# Peripherals.net
KiCad netlist of a schematic drawn in Altium Designer
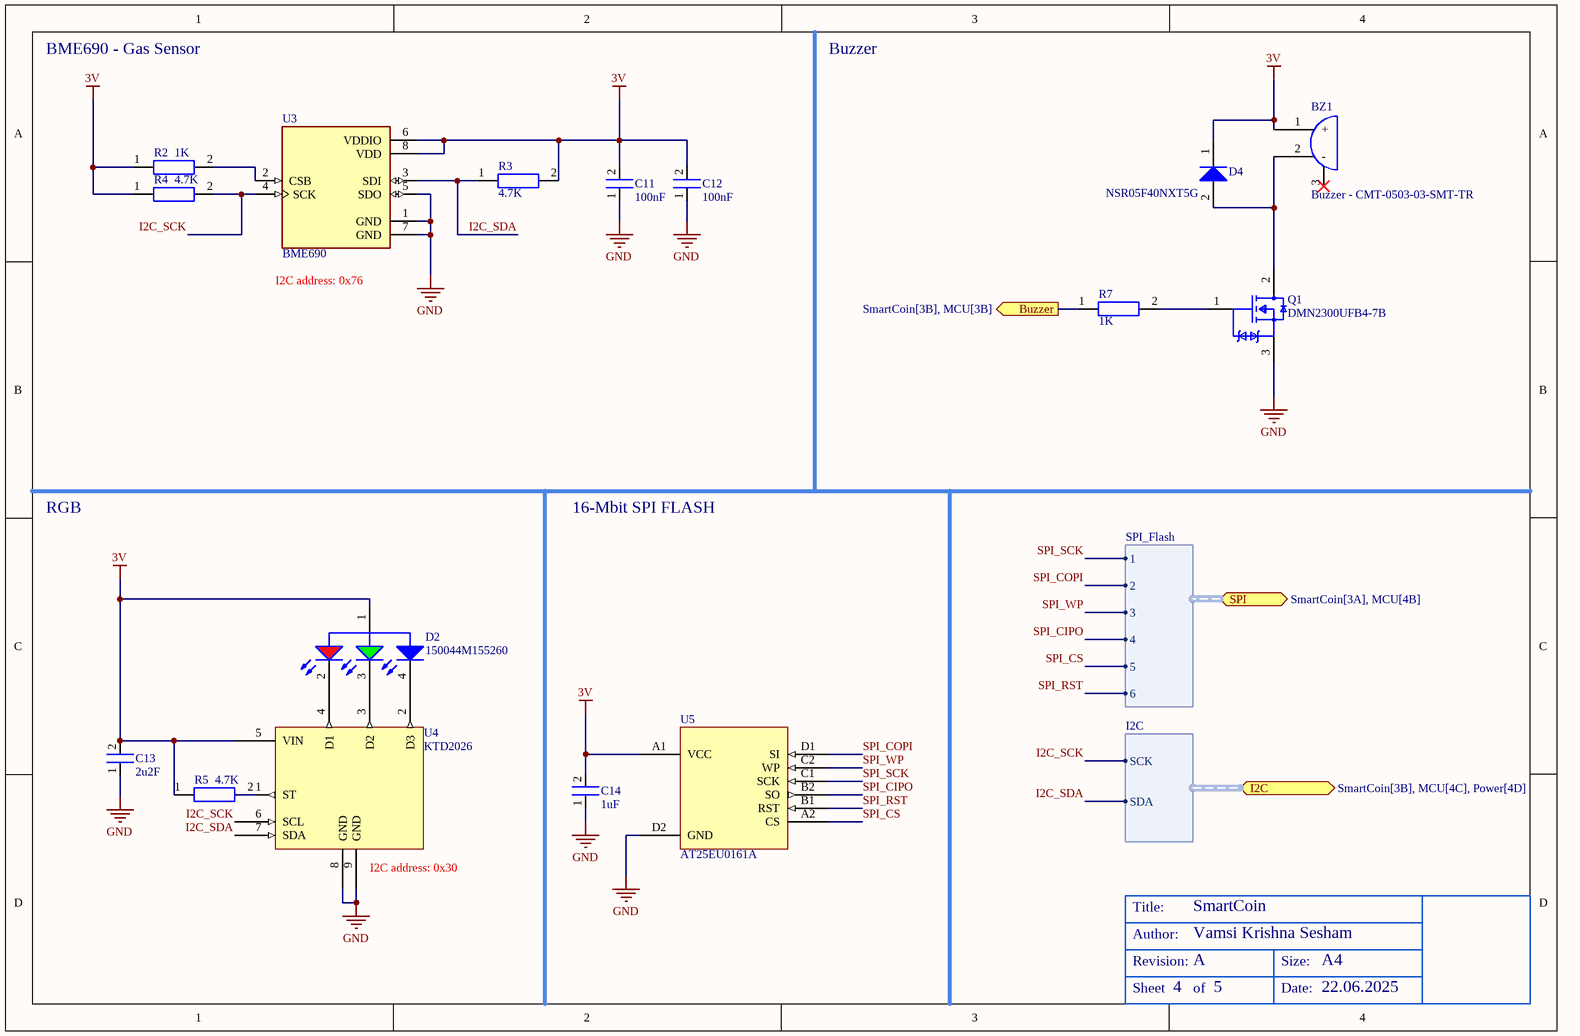
[diagram p0: Peripherals.SchDoc]

(export (version "E")
  (design (tool "Eeschema 10.0.6"))
  (components
    (comp (ref "BZ1")
      (value "Buzzer - CMT-0503-03-SMT-TR")
      (footprint "Buzzer - CMT-0503-03-SMT-TR")
      (description "MAGNETIC BUZZER TRANSDUCER")
      (libsource (lib "SmartCoin") (part "Buzzer - CMT-0503-03-SMT-TR"))
    )
    (comp (ref "C11")
      (value "100nF")
      (footprint "Capacitor - 0201")
      (libsource (lib "SmartCoin") (part "Capacitor - 0201"))
    )
    (comp (ref "C12")
      (value "100nF")
      (footprint "Capacitor - 0201")
      (libsource (lib "SmartCoin") (part "Capacitor - 0201"))
    )
    (comp (ref "C13")
      (value "2u2F")
      (footprint "Capacitor - 0201")
      (libsource (lib "SmartCoin") (part "Capacitor - 0201"))
    )
    (comp (ref "C14")
      (value "1uF")
      (footprint "Capacitor - 0201")
      (libsource (lib "SmartCoin") (part "Capacitor - 0201"))
    )
    (comp (ref "D2")
      (value "150044M155260")
      (footprint "WL-SFCC_0404_150044M155260")
      (description "150044M155260 WL-SFCC SMT Full-color Chip LED compact")
      (libsource (lib "Altium Content Vault") (part "WL-SFCC_150044M155260"))
    )
    (comp (ref "D4")
      (value "NSR05F40NXT5G")
      (footprint "ONSC-DSN-2-152AC-01_V")
      (description "Schottky Barrier Diode, 2-Pin DSN, Pb-Free, Tape and Reel")
      (fields (field (name "MANUFACTURER") "On Semiconductor"))
      (libsource (lib "Altium Content Vault") (part "ONSC-D-K1A2-2"))
    )
    (comp (ref "Q1")
      (value "DMN2300UFB4-7B")
      (footprint "FP-X2-DFN1006-3-MFG")
      (description "MOSFET N-CH 20V 1.3A 3DFN")
      (fields
        (field (name "MANUFACTURER") "Diodes Inc.")
        (field (name "OCTOPART") "https://octopart.com/dmn2300ufb4-7b-diodes+inc.-21789371")
      )
      (libsource (lib "Altium Content Vault") (part "a29196b179eec536a16aaf037fa858d"))
    )
    (comp (ref "R2")
      (value "1K")
      (footprint "Resistor - 0201")
      (libsource (lib "SmartCoin") (part "Resistor - 0201"))
    )
    (comp (ref "R3")
      (value "4.7K")
      (footprint "Resistor - 0201")
      (libsource (lib "SmartCoin") (part "Resistor - 0201"))
    )
    (comp (ref "R4")
      (value "4.7K")
      (footprint "Resistor - 0201")
      (libsource (lib "SmartCoin") (part "Resistor - 0201"))
    )
    (comp (ref "R5")
      (value "4.7K")
      (footprint "Resistor - 0201")
      (libsource (lib "SmartCoin") (part "Resistor - 0201"))
    )
    (comp (ref "R7")
      (value "1K")
      (footprint "Resistor - 0201")
      (libsource (lib "SmartCoin") (part "Resistor - 0201"))
    )
    (comp (ref "U3")
      (value "BME690")
      (footprint "IC_BME688")
      (description "Gas sensor measuring relative humidity, barometric pressure, ambient temperature and gas (VOC)")
      (fields (field (name "MP") "BME688"))
      (libsource (lib "Vamsi Krishna Sesham") (part "BME688"))
    )
    (comp (ref "U4")
      (value "KTD2026")
      (footprint "KTD2026")
      (description "3-CHANNEL Rgb Led Driver With I2C")
      (libsource (lib "SmartCoin") (part "KTD2026"))
    )
    (comp (ref "U5")
      (value "AT25EU0161A")
      (footprint "AT25EU0161A")
      (description "16-Mbit, Ultra-Low Energy Serial Flash Memory")
      (libsource (lib "SmartCoin") (part "AT25EU0161A"))
    )
  )
  (nets
    (net (code "3") (name "/Buzzer") (class "Default") (node (ref "R7") (pin "1") (pintype "passive")))
    (net (code "4") (name "/I2C_SCK") (class "Default")
      (node (ref "R4") (pin "2") (pintype "passive"))
      (node (ref "U3") (pin "4") (pinfunction "SCK_4") (pintype "input"))
      (node (ref "U4") (pin "6") (pinfunction "SCL_6") (pintype "input"))
    )
    (net (code "5") (name "/I2C_SDA") (class "Default")
      (node (ref "R3") (pin "1") (pintype "passive"))
      (node (ref "U3") (pin "3") (pinfunction "SDI_3") (pintype "bidirectional"))
      (node (ref "U4") (pin "7") (pinfunction "SDA_7") (pintype "input"))
    )
    (net (code "6") (name "/SPI_CIPO") (class "Default")
      (node (ref "U5") (pin "B2") (pinfunction "SO_B2") (pintype "output"))
    )
    (net (code "7") (name "/SPI_COPI") (class "Default")
      (node (ref "U5") (pin "D1") (pinfunction "SI_D1") (pintype "input"))
    )
    (net (code "8") (name "/SPI_CS") (class "Default")
      (node (ref "U5") (pin "A2") (pinfunction "CS_A2") (pintype "passive"))
    )
    (net (code "9") (name "/SPI_RST") (class "Default")
      (node (ref "U5") (pin "B1") (pinfunction "RST_B1") (pintype "input"))
    )
    (net (code "10") (name "/SPI_SCK") (class "Default")
      (node (ref "U5") (pin "C1") (pinfunction "SCK_C1") (pintype "input"))
    )
    (net (code "11") (name "/SPI_WP") (class "Default")
      (node (ref "U5") (pin "C2") (pinfunction "WP_C2") (pintype "input"))
    )
    (net (code "14") (name "3V") (class "Default")
      (node (ref "BZ1") (pin "1") (pinfunction "+_1") (pintype "passive"))
      (node (ref "C11") (pin "2") (pintype "passive"))
      (node (ref "C12") (pin "2") (pintype "passive"))
      (node (ref "C13") (pin "2") (pintype "passive"))
      (node (ref "C14") (pin "2") (pintype "passive"))
      (node (ref "D2") (pin "1") (pinfunction "A_1") (pintype "passive"))
      (node (ref "D4") (pin "1") (pinfunction "K_1") (pintype "passive"))
      (node (ref "R2") (pin "1") (pintype "passive"))
      (node (ref "R3") (pin "2") (pintype "passive"))
      (node (ref "R4") (pin "1") (pintype "passive"))
      (node (ref "R5") (pin "1") (pintype "passive"))
      (node (ref "U3") (pin "6") (pinfunction "VDDIO_6") (pintype "power_in"))
      (node (ref "U3") (pin "8") (pinfunction "VDD_8") (pintype "power_in"))
      (node (ref "U4") (pin "5") (pinfunction "VIN_5") (pintype "power_in"))
      (node (ref "U5") (pin "A1") (pinfunction "VCC_A1") (pintype "power_in"))
    )
    (net (code "15") (name "GND") (class "Default")
      (node (ref "C11") (pin "1") (pintype "passive"))
      (node (ref "C12") (pin "1") (pintype "passive"))
      (node (ref "C13") (pin "1") (pintype "passive"))
      (node (ref "C14") (pin "1") (pintype "passive"))
      (node (ref "Q1") (pin "3") (pinfunction "S_3") (pintype "passive"))
      (node (ref "U3") (pin "1") (pinfunction "GND_1") (pintype "power_in"))
      (node (ref "U3") (pin "5") (pinfunction "SDO_5") (pintype "bidirectional"))
      (node (ref "U3") (pin "7") (pinfunction "GND_7") (pintype "power_in"))
      (node (ref "U4") (pin "8") (pinfunction "GND_8") (pintype "power_in"))
      (node (ref "U4") (pin "9") (pinfunction "GND_9") (pintype "power_in"))
      (node (ref "U5") (pin "D2") (pinfunction "GND_D2") (pintype "power_in"))
    )
    (net (code "16") (name "Net-(BZ1--)") (class "Default")
      (node (ref "BZ1") (pin "2") (pinfunction "-_2") (pintype "passive"))
      (node (ref "D4") (pin "2") (pinfunction "A_2") (pintype "passive"))
      (node (ref "Q1") (pin "2") (pinfunction "D_2") (pintype "passive"))
    )
    (net (code "17") (name "Net-(Q1-G)") (class "Default")
      (node (ref "Q1") (pin "1") (pinfunction "G_1") (pintype "passive"))
      (node (ref "R7") (pin "2") (pintype "passive"))
    )
    (net (code "18") (name "Net-(U3-CSB)") (class "Default")
      (node (ref "R2") (pin "2") (pintype "passive"))
      (node (ref "U3") (pin "2") (pinfunction "CSB_2") (pintype "input"))
    )
    (net (code "19") (name "Net-(U4-D1)") (class "Default")
      (node (ref "D2") (pin "2") (pinfunction "K_2") (pintype "passive"))
      (node (ref "U4") (pin "4") (pinfunction "D1_4") (pintype "output"))
    )
    (net (code "20") (name "Net-(U4-D2)") (class "Default")
      (node (ref "D2") (pin "3") (pinfunction "K_3") (pintype "passive"))
      (node (ref "U4") (pin "3") (pinfunction "D2_3") (pintype "output"))
    )
    (net (code "21") (name "Net-(U4-D3)") (class "Default")
      (node (ref "D2") (pin "4") (pinfunction "K_4") (pintype "passive"))
      (node (ref "U4") (pin "2") (pinfunction "D3_2") (pintype "output"))
    )
    (net (code "22") (name "Net-(U4-ST)") (class "Default")
      (node (ref "R5") (pin "2") (pintype "passive"))
      (node (ref "U4") (pin "1") (pinfunction "ST_1") (pintype "output"))
    )
    (net (code "23") (name "unconnected-(BZ1-Pad3)") (class "Default")
      (node (ref "BZ1") (pin "3") (pintype "passive+no_connect"))
    )
  )
)
